# FMTrans.net
KiCad netlist of a schematic drawn in Altium Designer
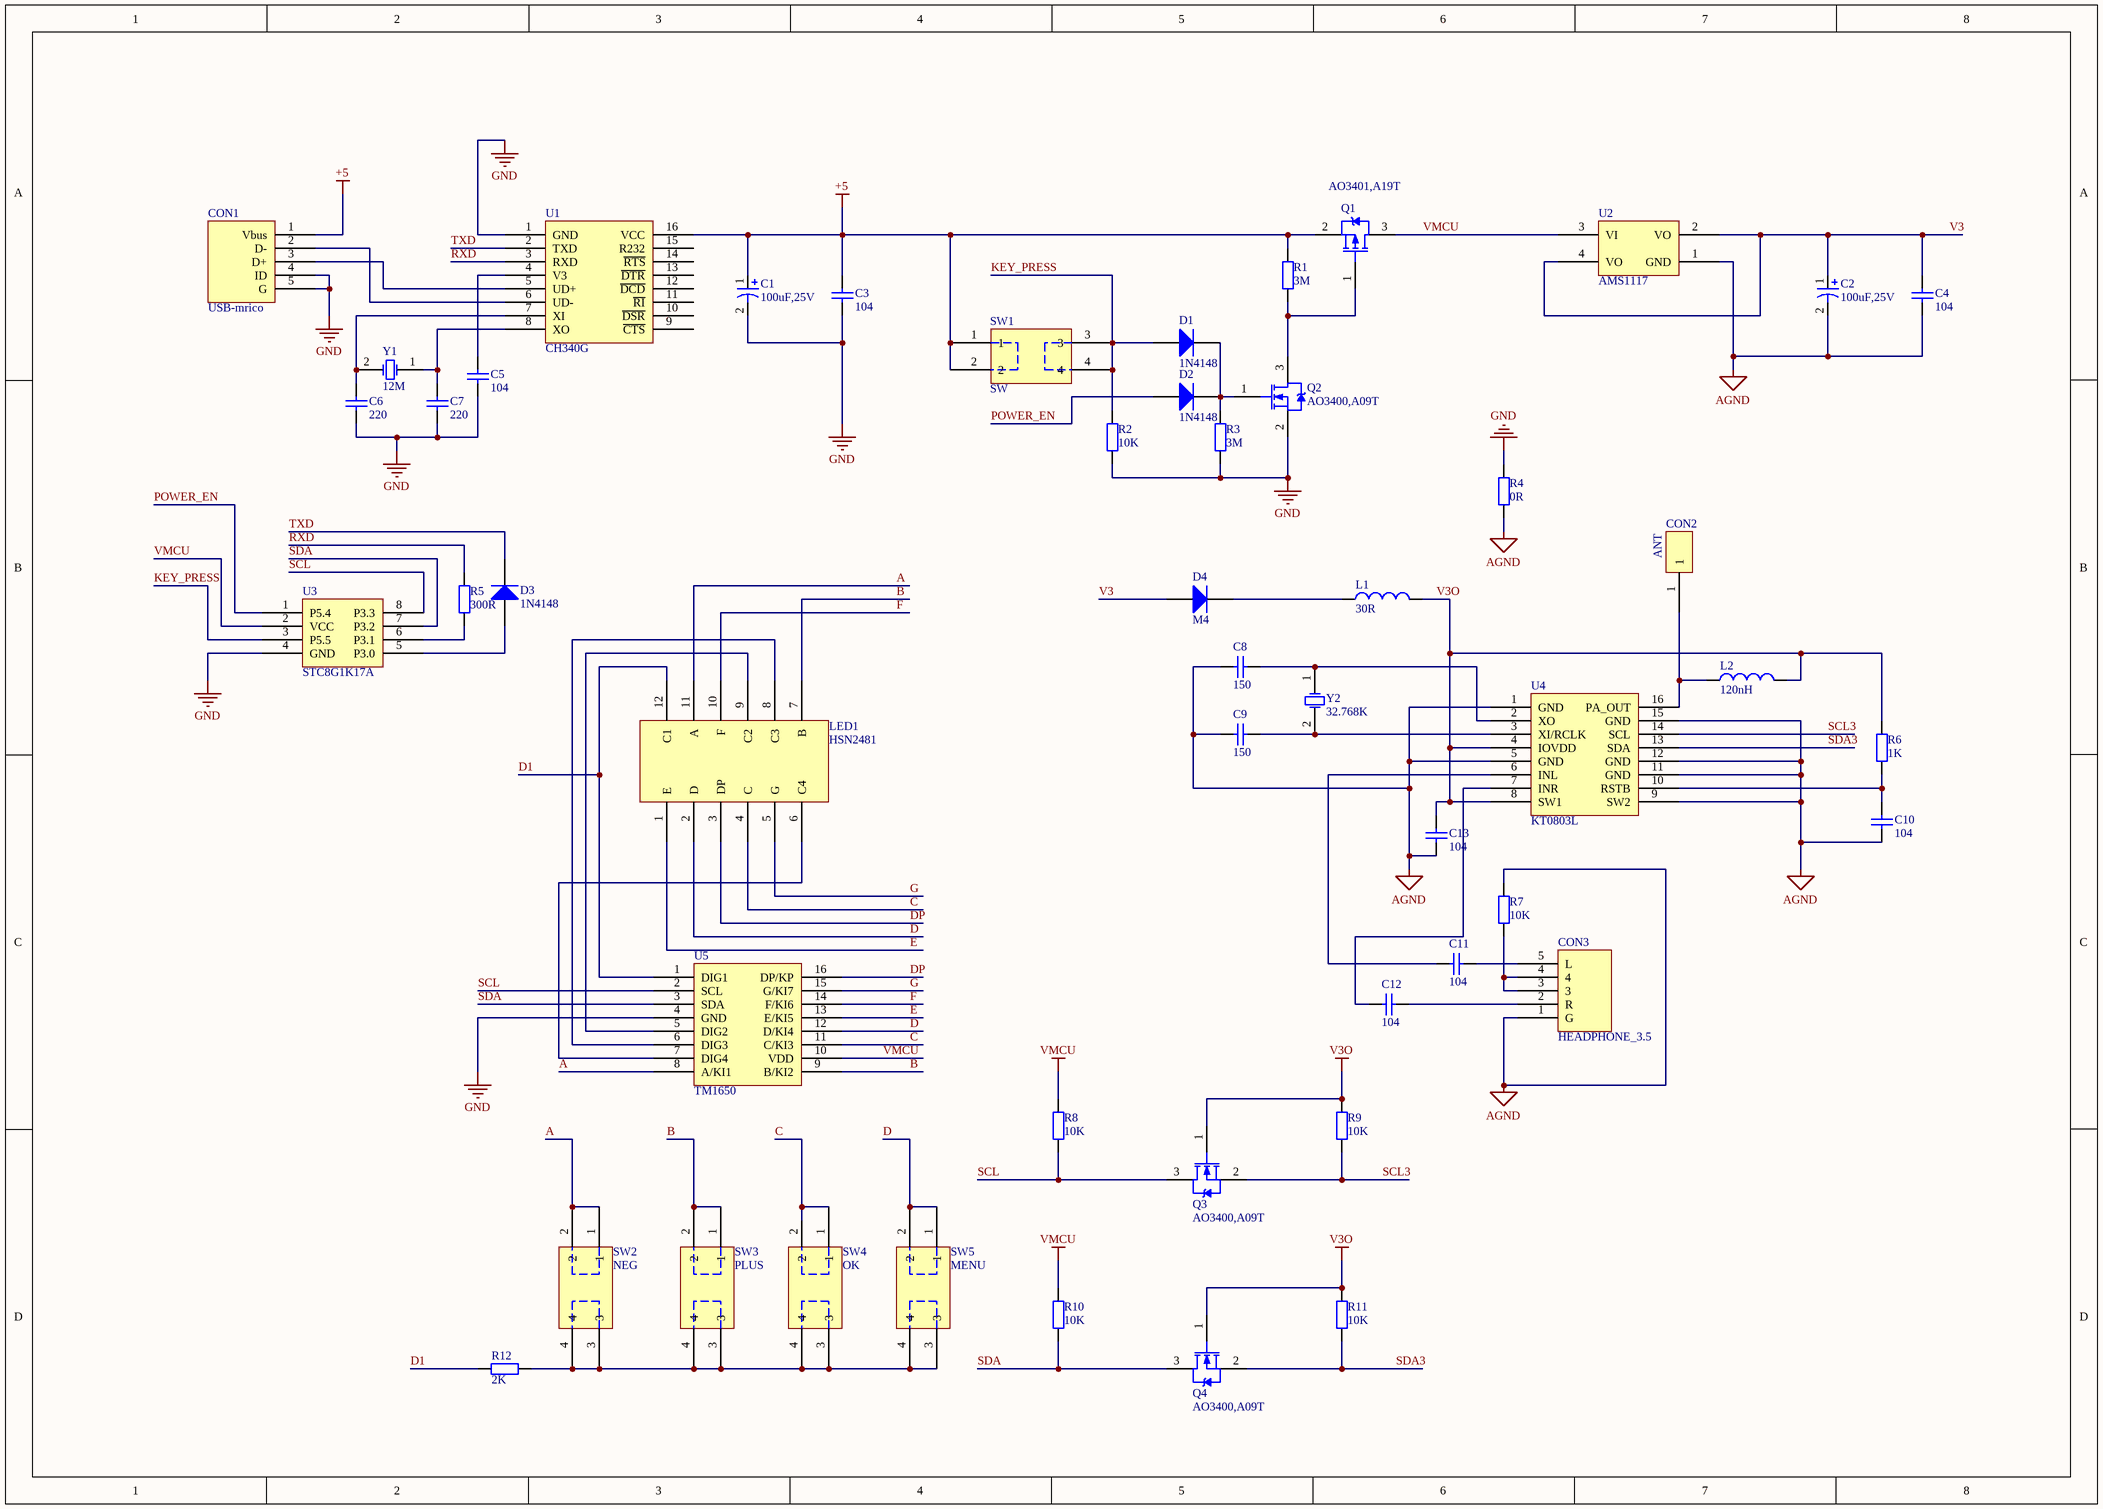
[diagram p0: FMTrans.SchDoc]

(export (version "E")
  (design (tool "Eeschema 10.0.6"))
  (components
    (comp (ref "C1")
      (value "100uF,25V")
      (footprint "FMTrans:SMD-EC-F6.3")
      (description "Polarized Capacitor (Radial)")
      (fields (field (name "Comment") "Cap Pol1") (field (name "PUBLISHER") "Altium Limited"))
      (libsource (lib "Miscellaneous Devices") (part "Cap Pol1"))
    )
    (comp (ref "C2")
      (value "100uF,25V")
      (footprint "FMTrans:SMD-EC-F6.3")
      (description "Polarized Capacitor (Radial)")
      (fields (field (name "Comment") "Cap Pol1") (field (name "PUBLISHER") "Altium Limited"))
      (libsource (lib "Miscellaneous Devices") (part "Cap Pol1"))
    )
    (comp (ref "C3")
      (value "104")
      (footprint "FMTrans:CAPC1608L")
      (description "Capacitor")
      (fields (field (name "Comment") "Cap") (field (name "PUBLISHER") "Altium Limited"))
      (libsource (lib "Miscellaneous Devices") (part "Cap"))
    )
    (comp (ref "C4")
      (value "104")
      (footprint "FMTrans:CAPC1608L")
      (description "Capacitor")
      (fields (field (name "Comment") "Cap") (field (name "PUBLISHER") "Altium Limited"))
      (libsource (lib "Miscellaneous Devices") (part "Cap"))
    )
    (comp (ref "C5")
      (value "104")
      (footprint "CAPC1608L")
      (description "Capacitor")
      (fields (field (name "Comment") "Cap") (field (name "PUBLISHER") "Altium Limited"))
      (libsource (lib "Miscellaneous Devices") (part "Cap"))
    )
    (comp (ref "C6")
      (value "220")
      (footprint "FMTrans:CAPC1608L")
      (description "Capacitor")
      (fields (field (name "Comment") "Cap") (field (name "PUBLISHER") "Altium Limited"))
      (libsource (lib "Miscellaneous Devices") (part "Cap"))
    )
    (comp (ref "C7")
      (value "220")
      (footprint "FMTrans:CAPC1608L")
      (description "Capacitor")
      (fields (field (name "Comment") "Cap") (field (name "PUBLISHER") "Altium Limited"))
      (libsource (lib "Miscellaneous Devices") (part "Cap"))
    )
    (comp (ref "C8")
      (value "150")
      (footprint "FMTrans:CAPC1608L")
      (description "Capacitor")
      (fields (field (name "Comment") "Cap") (field (name "PUBLISHER") "Altium Limited"))
      (libsource (lib "Miscellaneous Devices") (part "Cap"))
    )
    (comp (ref "C9")
      (value "150")
      (footprint "FMTrans:CAPC1608L")
      (description "Capacitor")
      (fields (field (name "Comment") "Cap") (field (name "PUBLISHER") "Altium Limited"))
      (libsource (lib "Miscellaneous Devices") (part "Cap"))
    )
    (comp (ref "C10")
      (value "104")
      (footprint "FMTrans:CAPC1608L")
      (description "Capacitor")
      (fields (field (name "Comment") "Cap") (field (name "PUBLISHER") "Altium Limited"))
      (libsource (lib "Miscellaneous Devices") (part "Cap"))
    )
    (comp (ref "C11")
      (value "104")
      (footprint "FMTrans:CAPC1608L")
      (description "Capacitor")
      (fields (field (name "Comment") "Cap") (field (name "PUBLISHER") "Altium Limited"))
      (libsource (lib "Miscellaneous Devices") (part "Cap"))
    )
    (comp (ref "C12")
      (value "104")
      (footprint "FMTrans:CAPC1608L")
      (description "Capacitor")
      (fields (field (name "Comment") "Cap") (field (name "PUBLISHER") "Altium Limited"))
      (libsource (lib "Miscellaneous Devices") (part "Cap"))
    )
    (comp (ref "C13")
      (value "104")
      (footprint "FMTrans:CAPC1608L")
      (description "Capacitor")
      (fields (field (name "Comment") "Cap") (field (name "PUBLISHER") "Altium Limited"))
      (libsource (lib "Miscellaneous Devices") (part "Cap"))
    )
    (comp (ref "CON1")
      (value "USB-mrico")
      (footprint "FMTrans:USB-micro_B")
      (libsource (lib "FMTrans") (part "USB_MICRO_B"))
    )
    (comp (ref "CON2") (value "ANT") (footprint "FMTrans:ANT") (libsource (lib "FMTrans") (part "ANT")))
    (comp (ref "CON3")
      (value "HEADPHONE_3.5")
      (footprint "FMTrans:3F07")
      (libsource (lib "FMTrans") (part "HEADPHONE_3.5"))
    )
    (comp (ref "D1")
      (value "1N4148")
      (footprint "FMTrans:CD3216-1206")
      (fields (field (name "PUBLISHER") "Altium Limited"))
      (libsource (lib "Miscellaneous Devices") (part "Diode"))
    )
    (comp (ref "D2")
      (value "1N4148")
      (footprint "FMTrans:CD3216-1206")
      (fields (field (name "PUBLISHER") "Altium Limited"))
      (libsource (lib "Miscellaneous Devices") (part "Diode"))
    )
    (comp (ref "D3")
      (value "1N4148")
      (footprint "FMTrans:CD3216-1206")
      (fields (field (name "PUBLISHER") "Altium Limited"))
      (libsource (lib "Miscellaneous Devices") (part "Diode"))
    )
    (comp (ref "D4")
      (value "M4")
      (footprint "FMTrans:CD3216-1206")
      (description "1N4148")
      (fields (field (name "PUBLISHER") "Altium Limited"))
      (libsource (lib "Miscellaneous Devices") (part "Diode"))
    )
    (comp (ref "L1")
      (value "30R")
      (footprint "FMTrans:RESC2012L")
      (description "Inductor")
      (fields (field (name "PUBLISHER") "Altium Limited"))
      (libsource (lib "Miscellaneous Devices") (part "Inductor"))
    )
    (comp (ref "L2")
      (value "120nH")
      (footprint "FMTrans:RESC2012L")
      (description "Inductor")
      (fields (field (name "PUBLISHER") "Altium Limited"))
      (libsource (lib "Miscellaneous Devices") (part "Inductor"))
    )
    (comp (ref "LED1")
      (value "HSN2481")
      (footprint "FMTrans:HSN2481")
      (libsource (lib "FMTrans") (part "HSN2481"))
    )
    (comp (ref "Q1")
      (value "AO3401,A19T")
      (footprint "FMTrans:SOT-23B_L")
      (description "P-Channel Power MOSFET")
      (fields (field (name "PUBLISHER") "Altium Limited"))
      (libsource (lib "Miscellaneous Devices") (part "PMOS-2"))
    )
    (comp (ref "Q2")
      (value "AO3400,A09T")
      (footprint "FMTrans:SOT-23B_L")
      (description "N-Channel Power MOSFET")
      (fields (field (name "PUBLISHER") "Altium Limited"))
      (libsource (lib "Miscellaneous Devices") (part "NMOS-2"))
    )
    (comp (ref "Q3")
      (value "AO3400,A09T")
      (footprint "FMTrans:SOT-23B_L")
      (description "N-Channel Power MOSFET")
      (fields (field (name "PUBLISHER") "Altium Limited"))
      (libsource (lib "Miscellaneous Devices") (part "NMOS-2"))
    )
    (comp (ref "Q4")
      (value "AO3400,A09T")
      (footprint "FMTrans:SOT-23B_L")
      (description "N-Channel Power MOSFET")
      (fields (field (name "PUBLISHER") "Altium Limited"))
      (libsource (lib "Miscellaneous Devices") (part "NMOS-2"))
    )
    (comp (ref "R1")
      (value "3M")
      (footprint "FMTrans:RESC1608L")
      (description "Resistor")
      (fields (field (name "Comment") "Res2") (field (name "PUBLISHER") "Altium Limited"))
      (libsource (lib "Miscellaneous Devices") (part "Res2"))
    )
    (comp (ref "R2")
      (value "10K")
      (footprint "FMTrans:RESC1608L")
      (description "Resistor")
      (fields (field (name "Comment") "Res2") (field (name "PUBLISHER") "Altium Limited"))
      (libsource (lib "Miscellaneous Devices") (part "Res2"))
    )
    (comp (ref "R3")
      (value "3M")
      (footprint "FMTrans:RESC1608L")
      (description "Resistor")
      (fields (field (name "Comment") "Res2") (field (name "PUBLISHER") "Altium Limited"))
      (libsource (lib "Miscellaneous Devices") (part "Res2"))
    )
    (comp (ref "R4")
      (value "0R")
      (footprint "FMTrans:RESC1608L")
      (description "Resistor")
      (fields (field (name "Comment") "Res2") (field (name "PUBLISHER") "Altium Limited"))
      (libsource (lib "Miscellaneous Devices") (part "Res2"))
    )
    (comp (ref "R5")
      (value "300R")
      (footprint "FMTrans:RESC1608L")
      (description "Resistor")
      (fields (field (name "Comment") "Res2") (field (name "PUBLISHER") "Altium Limited"))
      (libsource (lib "Miscellaneous Devices") (part "Res2"))
    )
    (comp (ref "R6")
      (value "1K")
      (footprint "FMTrans:RESC1608L")
      (description "Resistor")
      (fields (field (name "Comment") "Res2") (field (name "PUBLISHER") "Altium Limited"))
      (libsource (lib "Miscellaneous Devices") (part "Res2"))
    )
    (comp (ref "R7")
      (value "10K")
      (footprint "FMTrans:RESC1608L")
      (description "Resistor")
      (fields (field (name "Comment") "Res2") (field (name "PUBLISHER") "Altium Limited"))
      (libsource (lib "Miscellaneous Devices") (part "Res2"))
    )
    (comp (ref "R8")
      (value "10K")
      (footprint "FMTrans:RESC1608L")
      (description "Resistor")
      (fields (field (name "Comment") "Res2") (field (name "PUBLISHER") "Altium Limited"))
      (libsource (lib "Miscellaneous Devices") (part "Res2"))
    )
    (comp (ref "R9")
      (value "10K")
      (footprint "FMTrans:RESC1608L")
      (description "Resistor")
      (fields (field (name "Comment") "Res2") (field (name "PUBLISHER") "Altium Limited"))
      (libsource (lib "Miscellaneous Devices") (part "Res2"))
    )
    (comp (ref "R10")
      (value "10K")
      (footprint "FMTrans:RESC1608L")
      (description "Resistor")
      (fields (field (name "Comment") "Res2") (field (name "PUBLISHER") "Altium Limited"))
      (libsource (lib "Miscellaneous Devices") (part "Res2"))
    )
    (comp (ref "R11")
      (value "10K")
      (footprint "FMTrans:RESC1608L")
      (description "Resistor")
      (fields (field (name "Comment") "Res2") (field (name "PUBLISHER") "Altium Limited"))
      (libsource (lib "Miscellaneous Devices") (part "Res2"))
    )
    (comp (ref "R12")
      (value "2K")
      (footprint "FMTrans:RESC1608L")
      (description "Resistor")
      (fields (field (name "Comment") "Res2") (field (name "PUBLISHER") "Altium Limited"))
      (libsource (lib "") (part "Res2_1"))
    )
    (comp (ref "SW1")
      (value "SW")
      (footprint "FMTrans:SW/PB-V4/H7.1")
      (libsource (lib "FMTrans") (part "SW"))
    )
    (comp (ref "SW2")
      (value "NEG")
      (footprint "FMTrans:SW/PB-V4/H7.1")
      (description "SW")
      (libsource (lib "") (part "SW_1"))
    )
    (comp (ref "SW3")
      (value "PLUS")
      (footprint "FMTrans:SW/PB-V4/H7.1")
      (description "SW")
      (libsource (lib "") (part "SW_1"))
    )
    (comp (ref "SW4")
      (value "OK")
      (footprint "FMTrans:SW/PB-V4/H7.1")
      (description "SW")
      (libsource (lib "") (part "SW_1"))
    )
    (comp (ref "SW5")
      (value "MENU")
      (footprint "FMTrans:SW/PB-V4/H7.1")
      (description "SW")
      (libsource (lib "") (part "SW_1"))
    )
    (comp (ref "U1")
      (value "CH340G")
      (footprint "FMTrans:SOP127P762-16L")
      (libsource (lib "FMTrans") (part "CH340G"))
    )
    (comp (ref "U2")
      (value "AMS1117")
      (footprint "FMTrans:SOT223-4M")
      (libsource (lib "FMTrans") (part "AMS1117"))
    )
    (comp (ref "U3")
      (value "STC8G1K17A")
      (footprint "FMTrans:DIP-8")
      (libsource (lib "FMTrans") (part "STC8G1K17A"))
    )
    (comp (ref "U4")
      (value "KT0803L")
      (footprint "FMTrans:SOP127P762-16L")
      (libsource (lib "FMTrans") (part "KT0803L"))
    )
    (comp (ref "U5")
      (value "TM1650")
      (footprint "FMTrans:SOP127P762-16L")
      (libsource (lib "FMTrans") (part "TM1650"))
    )
    (comp (ref "Y1")
      (value "12M")
      (footprint "FMTrans:XTAL-5032")
      (description "Crystal Oscillator")
      (fields (field (name "PUBLISHER") "Altium Limited"))
      (libsource (lib "Miscellaneous Devices") (part "XTAL"))
    )
    (comp (ref "Y2")
      (value "32.768K")
      (footprint "FMTrans:XTAL-3215")
      (description "Crystal Oscillator")
      (fields (field (name "PUBLISHER") "Altium Limited"))
      (libsource (lib "Miscellaneous Devices") (part "XTAL"))
    )
  )
  (nets
    (net (code "1") (name "+5") (class "Default")
      (node (ref "C1") (pin "1") (pinfunction "1_1") (pintype "passive"))
      (node (ref "C3") (pin "2") (pinfunction "2_2") (pintype "passive"))
      (node (ref "CON1") (pin "1") (pinfunction "Vbus_1") (pintype "passive"))
      (node (ref "Q1") (pin "2") (pinfunction "S_2") (pintype "passive"))
      (node (ref "R1") (pin "2") (pinfunction "2_2") (pintype "passive"))
      (node (ref "SW1") (pin "1") (pinfunction "1_1") (pintype "passive"))
      (node (ref "SW1") (pin "2") (pinfunction "2_2") (pintype "passive"))
      (node (ref "U1") (pin "16") (pinfunction "VCC_16") (pintype "passive"))
    )
    (net (code "2") (name "/A") (class "Default")
      (node (ref "LED1") (pin "11") (pinfunction "A_11") (pintype "passive"))
      (node (ref "SW2") (pin "1") (pinfunction "1_1") (pintype "passive"))
      (node (ref "SW2") (pin "2") (pinfunction "2_2") (pintype "passive"))
      (node (ref "U5") (pin "8") (pinfunction "A/KI1_8") (pintype "passive"))
    )
    (net (code "3") (name "/B") (class "Default")
      (node (ref "LED1") (pin "7") (pinfunction "B_7") (pintype "passive"))
      (node (ref "SW3") (pin "1") (pinfunction "1_1") (pintype "passive"))
      (node (ref "SW3") (pin "2") (pinfunction "2_2") (pintype "passive"))
      (node (ref "U5") (pin "9") (pinfunction "B/KI2_9") (pintype "passive"))
    )
    (net (code "4") (name "/C") (class "Default")
      (node (ref "LED1") (pin "4") (pinfunction "C_4") (pintype "passive"))
      (node (ref "SW4") (pin "1") (pinfunction "1_1") (pintype "passive"))
      (node (ref "SW4") (pin "2") (pinfunction "2_2") (pintype "passive"))
      (node (ref "U5") (pin "11") (pinfunction "C/KI3_11") (pintype "passive"))
    )
    (net (code "5") (name "/D") (class "Default")
      (node (ref "LED1") (pin "2") (pinfunction "D_2") (pintype "passive"))
      (node (ref "SW5") (pin "1") (pinfunction "1_1") (pintype "passive"))
      (node (ref "SW5") (pin "2") (pinfunction "2_2") (pintype "passive"))
      (node (ref "U5") (pin "12") (pinfunction "D/KI4_12") (pintype "passive"))
    )
    (net (code "6") (name "/D1") (class "Default")
      (node (ref "LED1") (pin "12") (pinfunction "C1_12") (pintype "passive"))
      (node (ref "R12") (pin "2") (pinfunction "2_2") (pintype "passive"))
      (node (ref "U5") (pin "1") (pinfunction "DIG1_1") (pintype "passive"))
    )
    (net (code "7") (name "/DP") (class "Default")
      (node (ref "LED1") (pin "3") (pinfunction "DP_3") (pintype "passive"))
      (node (ref "U5") (pin "16") (pinfunction "DP/KP_16") (pintype "passive"))
    )
    (net (code "8") (name "/E") (class "Default")
      (node (ref "LED1") (pin "1") (pinfunction "E_1") (pintype "passive"))
      (node (ref "U5") (pin "13") (pinfunction "E/KI5_13") (pintype "passive"))
    )
    (net (code "9") (name "/F") (class "Default")
      (node (ref "LED1") (pin "10") (pinfunction "F_10") (pintype "passive"))
      (node (ref "U5") (pin "14") (pinfunction "F/KI6_14") (pintype "passive"))
    )
    (net (code "10") (name "/G") (class "Default")
      (node (ref "LED1") (pin "5") (pinfunction "G_5") (pintype "passive"))
      (node (ref "U5") (pin "15") (pinfunction "G/KI7_15") (pintype "passive"))
    )
    (net (code "11") (name "/KEY_PRESS") (class "Default")
      (node (ref "D1") (pin "1") (pinfunction "A_1") (pintype "passive"))
      (node (ref "R2") (pin "2") (pinfunction "2_2") (pintype "passive"))
      (node (ref "SW1") (pin "3") (pinfunction "3_3") (pintype "passive"))
      (node (ref "SW1") (pin "4") (pinfunction "4_4") (pintype "passive"))
      (node (ref "U3") (pin "3") (pinfunction "P5.5_3") (pintype "passive"))
    )
    (net (code "12") (name "/POWER_EN") (class "Default")
      (node (ref "D2") (pin "1") (pinfunction "A_1") (pintype "passive"))
      (node (ref "U3") (pin "1") (pinfunction "P5.4_1") (pintype "passive"))
    )
    (net (code "13") (name "/RXD") (class "Default")
      (node (ref "R5") (pin "2") (pinfunction "2_2") (pintype "passive"))
      (node (ref "U1") (pin "3") (pinfunction "RXD_3") (pintype "passive"))
    )
    (net (code "14") (name "/SCL") (class "Default")
      (node (ref "Q3") (pin "3") (pinfunction "D_3") (pintype "passive"))
      (node (ref "R8") (pin "1") (pinfunction "1_1") (pintype "passive"))
      (node (ref "U3") (pin "8") (pinfunction "P3.3_8") (pintype "passive"))
      (node (ref "U5") (pin "2") (pinfunction "SCL_2") (pintype "passive"))
    )
    (net (code "15") (name "/SCL3") (class "Default")
      (node (ref "Q3") (pin "2") (pinfunction "S_2") (pintype "passive"))
      (node (ref "R9") (pin "1") (pinfunction "1_1") (pintype "passive"))
      (node (ref "U4") (pin "14") (pinfunction "SCL_14") (pintype "passive"))
    )
    (net (code "16") (name "/SDA") (class "Default")
      (node (ref "Q4") (pin "3") (pinfunction "D_3") (pintype "passive"))
      (node (ref "R10") (pin "1") (pinfunction "1_1") (pintype "passive"))
      (node (ref "U3") (pin "7") (pinfunction "P3.2_7") (pintype "passive"))
      (node (ref "U5") (pin "3") (pinfunction "SDA_3") (pintype "passive"))
    )
    (net (code "17") (name "/SDA3") (class "Default")
      (node (ref "Q4") (pin "2") (pinfunction "S_2") (pintype "passive"))
      (node (ref "R11") (pin "1") (pinfunction "1_1") (pintype "passive"))
      (node (ref "U4") (pin "13") (pinfunction "SDA_13") (pintype "passive"))
    )
    (net (code "18") (name "/TXD") (class "Default")
      (node (ref "D3") (pin "2") (pinfunction "K_2") (pintype "passive"))
      (node (ref "U1") (pin "2") (pinfunction "TXD_2") (pintype "passive"))
    )
    (net (code "19") (name "/V3") (class "Default")
      (node (ref "C2") (pin "1") (pinfunction "1_1") (pintype "passive"))
      (node (ref "C4") (pin "2") (pinfunction "2_2") (pintype "passive"))
      (node (ref "D4") (pin "1") (pinfunction "A_1") (pintype "passive"))
      (node (ref "U2") (pin "2") (pinfunction "VO_2") (pintype "passive"))
      (node (ref "U2") (pin "4") (pinfunction "VO_4") (pintype "passive"))
    )
    (net (code "20") (name "AGND") (class "Default")
      (node (ref "C10") (pin "2") (pinfunction "2_2") (pintype "passive"))
      (node (ref "C13") (pin "1") (pinfunction "1_1") (pintype "passive"))
      (node (ref "C2") (pin "2") (pinfunction "2_2") (pintype "passive"))
      (node (ref "C4") (pin "1") (pinfunction "1_1") (pintype "passive"))
      (node (ref "C8") (pin "1") (pinfunction "1_1") (pintype "passive"))
      (node (ref "C9") (pin "1") (pinfunction "1_1") (pintype "passive"))
      (node (ref "CON3") (pin "1") (pinfunction "G_1") (pintype "passive"))
      (node (ref "R4") (pin "1") (pinfunction "1_1") (pintype "passive"))
      (node (ref "R7") (pin "2") (pinfunction "2_2") (pintype "passive"))
      (node (ref "U2") (pin "1") (pinfunction "GND_1") (pintype "passive"))
      (node (ref "U4") (pin "1") (pinfunction "GND_1") (pintype "passive"))
      (node (ref "U4") (pin "11") (pinfunction "GND_11") (pintype "passive"))
      (node (ref "U4") (pin "12") (pinfunction "GND_12") (pintype "passive"))
      (node (ref "U4") (pin "15") (pinfunction "GND_15") (pintype "passive"))
      (node (ref "U4") (pin "5") (pinfunction "GND_5") (pintype "passive"))
      (node (ref "U4") (pin "9") (pinfunction "SW2_9") (pintype "passive"))
    )
    (net (code "21") (name "GND") (class "Default")
      (node (ref "C1") (pin "2") (pinfunction "2_2") (pintype "passive"))
      (node (ref "C3") (pin "1") (pinfunction "1_1") (pintype "passive"))
      (node (ref "C5") (pin "1") (pinfunction "1_1") (pintype "passive"))
      (node (ref "C6") (pin "1") (pinfunction "1_1") (pintype "passive"))
      (node (ref "C7") (pin "1") (pinfunction "1_1") (pintype "passive"))
      (node (ref "CON1") (pin "4") (pinfunction "ID_4") (pintype "passive"))
      (node (ref "CON1") (pin "5") (pinfunction "G_5") (pintype "passive"))
      (node (ref "Q2") (pin "2") (pinfunction "S_2") (pintype "passive"))
      (node (ref "R2") (pin "1") (pinfunction "1_1") (pintype "passive"))
      (node (ref "R3") (pin "1") (pinfunction "1_1") (pintype "passive"))
      (node (ref "R4") (pin "2") (pinfunction "2_2") (pintype "passive"))
      (node (ref "U1") (pin "1") (pinfunction "GND_1") (pintype "passive"))
      (node (ref "U3") (pin "4") (pinfunction "GND_4") (pintype "passive"))
      (node (ref "U5") (pin "4") (pinfunction "GND_4") (pintype "passive"))
    )
    (net (code "22") (name "Net-(CON1-D+)") (class "Default")
      (node (ref "CON1") (pin "3") (pinfunction "D+_3") (pintype "passive"))
      (node (ref "U1") (pin "5") (pinfunction "UD+_5") (pintype "passive"))
    )
    (net (code "23") (name "Net-(CON1-D-)") (class "Default")
      (node (ref "CON1") (pin "2") (pinfunction "D-_2") (pintype "passive"))
      (node (ref "U1") (pin "6") (pinfunction "UD-_6") (pintype "passive"))
    )
    (net (code "24") (name "Net-(CON3-L)") (class "Default")
      (node (ref "C11") (pin "1") (pinfunction "1_1") (pintype "passive"))
      (node (ref "CON3") (pin "5") (pinfunction "L_5") (pintype "passive"))
    )
    (net (code "25") (name "Net-(CON3-Pad3)") (class "Default")
      (node (ref "CON3") (pin "3") (pinfunction "3_3") (pintype "passive"))
      (node (ref "CON3") (pin "4") (pinfunction "4_4") (pintype "passive"))
      (node (ref "R7") (pin "1") (pinfunction "1_1") (pintype "passive"))
    )
    (net (code "26") (name "Net-(CON3-R)") (class "Default")
      (node (ref "C12") (pin "1") (pinfunction "1_1") (pintype "passive"))
      (node (ref "CON3") (pin "2") (pinfunction "R_2") (pintype "passive"))
    )
    (net (code "27") (name "Net-(D1-K)") (class "Default")
      (node (ref "D1") (pin "2") (pinfunction "K_2") (pintype "passive"))
      (node (ref "D2") (pin "2") (pinfunction "K_2") (pintype "passive"))
      (node (ref "Q2") (pin "1") (pinfunction "G_1") (pintype "passive"))
      (node (ref "R3") (pin "2") (pinfunction "2_2") (pintype "passive"))
    )
    (net (code "28") (name "Net-(D3-A)") (class "Default")
      (node (ref "D3") (pin "1") (pinfunction "A_1") (pintype "passive"))
      (node (ref "U3") (pin "5") (pinfunction "P3.0_5") (pintype "passive"))
    )
    (net (code "29") (name "Net-(D4-K)") (class "Default")
      (node (ref "D4") (pin "2") (pinfunction "K_2") (pintype "passive"))
      (node (ref "L1") (pin "1") (pinfunction "1_1") (pintype "passive"))
    )
    (net (code "30") (name "Net-(LED1-C2)") (class "Default")
      (node (ref "LED1") (pin "9") (pinfunction "C2_9") (pintype "passive"))
      (node (ref "U5") (pin "5") (pinfunction "DIG2_5") (pintype "passive"))
    )
    (net (code "31") (name "Net-(LED1-C3)") (class "Default")
      (node (ref "LED1") (pin "8") (pinfunction "C3_8") (pintype "passive"))
      (node (ref "U5") (pin "6") (pinfunction "DIG3_6") (pintype "passive"))
    )
    (net (code "32") (name "Net-(LED1-C4)") (class "Default")
      (node (ref "LED1") (pin "6") (pinfunction "C4_6") (pintype "passive"))
      (node (ref "U5") (pin "7") (pinfunction "DIG4_7") (pintype "passive"))
    )
    (net (code "33") (name "Net-(Q1-G)") (class "Default")
      (node (ref "Q1") (pin "1") (pinfunction "G_1") (pintype "passive"))
      (node (ref "Q2") (pin "3") (pinfunction "D_3") (pintype "passive"))
      (node (ref "R1") (pin "1") (pinfunction "1_1") (pintype "passive"))
    )
    (net (code "34") (name "Net-(R12-Pad1)") (class "Default")
      (node (ref "R12") (pin "1") (pinfunction "1_1") (pintype "passive"))
      (node (ref "SW2") (pin "3") (pinfunction "3_3") (pintype "passive"))
      (node (ref "SW2") (pin "4") (pinfunction "4_4") (pintype "passive"))
      (node (ref "SW3") (pin "3") (pinfunction "3_3") (pintype "passive"))
      (node (ref "SW3") (pin "4") (pinfunction "4_4") (pintype "passive"))
      (node (ref "SW4") (pin "3") (pinfunction "3_3") (pintype "passive"))
      (node (ref "SW4") (pin "4") (pinfunction "4_4") (pintype "passive"))
      (node (ref "SW5") (pin "3") (pinfunction "3_3") (pintype "passive"))
      (node (ref "SW5") (pin "4") (pinfunction "4_4") (pintype "passive"))
    )
    (net (code "35") (name "Net-(U1-V3)") (class "Default")
      (node (ref "C5") (pin "2") (pinfunction "2_2") (pintype "passive"))
      (node (ref "U1") (pin "4") (pinfunction "V3_4") (pintype "passive"))
    )
    (net (code "36") (name "Net-(U1-XI)") (class "Default")
      (node (ref "C6") (pin "2") (pinfunction "2_2") (pintype "passive"))
      (node (ref "U1") (pin "7") (pinfunction "XI_7") (pintype "passive"))
      (node (ref "Y1") (pin "2") (pinfunction "OSC2_2") (pintype "passive"))
    )
    (net (code "37") (name "Net-(U1-XO)") (class "Default")
      (node (ref "C7") (pin "2") (pinfunction "2_2") (pintype "passive"))
      (node (ref "U1") (pin "8") (pinfunction "XO_8") (pintype "passive"))
      (node (ref "Y1") (pin "1") (pinfunction "OSC1_1") (pintype "passive"))
    )
    (net (code "38") (name "Net-(U3-P3.1)") (class "Default")
      (node (ref "R5") (pin "1") (pinfunction "1_1") (pintype "passive"))
      (node (ref "U3") (pin "6") (pinfunction "P3.1_6") (pintype "passive"))
    )
    (net (code "39") (name "Net-(U4-INL)") (class "Default")
      (node (ref "C11") (pin "2") (pinfunction "2_2") (pintype "passive"))
      (node (ref "U4") (pin "6") (pinfunction "INL_6") (pintype "passive"))
    )
    (net (code "40") (name "Net-(U4-INR)") (class "Default")
      (node (ref "C12") (pin "2") (pinfunction "2_2") (pintype "passive"))
      (node (ref "U4") (pin "7") (pinfunction "INR_7") (pintype "passive"))
    )
    (net (code "41") (name "Net-(U4-PA_OUT)") (class "Default")
      (node (ref "CON2") (pin "1") (pinfunction "1_1") (pintype "passive"))
      (node (ref "L2") (pin "1") (pinfunction "1_1") (pintype "passive"))
      (node (ref "U4") (pin "16") (pinfunction "PA_OUT_16") (pintype "passive"))
    )
    (net (code "42") (name "Net-(U4-RSTB)") (class "Default")
      (node (ref "C10") (pin "1") (pinfunction "1_1") (pintype "passive"))
      (node (ref "R6") (pin "1") (pinfunction "1_1") (pintype "passive"))
      (node (ref "U4") (pin "10") (pinfunction "RSTB_10") (pintype "passive"))
    )
    (net (code "43") (name "Net-(U4-XI{slash}RCLK)") (class "Default")
      (node (ref "C9") (pin "2") (pinfunction "2_2") (pintype "passive"))
      (node (ref "U4") (pin "3") (pinfunction "XI/RCLK_3") (pintype "passive"))
      (node (ref "Y2") (pin "2") (pinfunction "OSC2_2") (pintype "passive"))
    )
    (net (code "44") (name "Net-(U4-XO)") (class "Default")
      (node (ref "C8") (pin "2") (pinfunction "2_2") (pintype "passive"))
      (node (ref "U4") (pin "2") (pinfunction "XO_2") (pintype "passive"))
      (node (ref "Y2") (pin "1") (pinfunction "OSC1_1") (pintype "passive"))
    )
    (net (code "45") (name "V3O") (class "Default")
      (node (ref "C13") (pin "2") (pinfunction "2_2") (pintype "passive"))
      (node (ref "L1") (pin "2") (pinfunction "2_2") (pintype "passive"))
      (node (ref "L2") (pin "2") (pinfunction "2_2") (pintype "passive"))
      (node (ref "Q3") (pin "1") (pinfunction "G_1") (pintype "passive"))
      (node (ref "Q4") (pin "1") (pinfunction "G_1") (pintype "passive"))
      (node (ref "R11") (pin "2") (pinfunction "2_2") (pintype "passive"))
      (node (ref "R6") (pin "2") (pinfunction "2_2") (pintype "passive"))
      (node (ref "R9") (pin "2") (pinfunction "2_2") (pintype "passive"))
      (node (ref "U4") (pin "4") (pinfunction "IOVDD_4") (pintype "passive"))
      (node (ref "U4") (pin "8") (pinfunction "SW1_8") (pintype "passive"))
    )
    (net (code "46") (name "VMCU") (class "Default")
      (node (ref "Q1") (pin "3") (pinfunction "D_3") (pintype "passive"))
      (node (ref "R10") (pin "2") (pinfunction "2_2") (pintype "passive"))
      (node (ref "R8") (pin "2") (pinfunction "2_2") (pintype "passive"))
      (node (ref "U2") (pin "3") (pinfunction "VI_3") (pintype "passive"))
      (node (ref "U3") (pin "2") (pinfunction "VCC_2") (pintype "passive"))
      (node (ref "U5") (pin "10") (pinfunction "VDD_10") (pintype "passive"))
    )
    (net (code "47") (name "unconnected-(U1-R232-Pad15)") (class "Default")
      (node (ref "U1") (pin "15") (pinfunction "R232_15") (pintype "passive"))
    )
    (net (code "48") (name "unconnected-(U1-~{CTS}-Pad9)") (class "Default")
      (node (ref "U1") (pin "9") (pinfunction "~{CTS}_9") (pintype "passive"))
    )
    (net (code "49") (name "unconnected-(U1-~{DCD}-Pad12)") (class "Default")
      (node (ref "U1") (pin "12") (pinfunction "~{DCD}_12") (pintype "passive"))
    )
    (net (code "50") (name "unconnected-(U1-~{DSR}-Pad10)") (class "Default")
      (node (ref "U1") (pin "10") (pinfunction "~{DSR}_10") (pintype "passive"))
    )
    (net (code "51") (name "unconnected-(U1-~{DTR}-Pad13)") (class "Default")
      (node (ref "U1") (pin "13") (pinfunction "~{DTR}_13") (pintype "passive"))
    )
    (net (code "52") (name "unconnected-(U1-~{RI}-Pad11)") (class "Default")
      (node (ref "U1") (pin "11") (pinfunction "~{RI}_11") (pintype "passive"))
    )
    (net (code "53") (name "unconnected-(U1-~{RTS}-Pad14)") (class "Default")
      (node (ref "U1") (pin "14") (pinfunction "~{RTS}_14") (pintype "passive"))
    )
  )
)
